# OpenBook_Schematic.net
KiCad netlist of a schematic drawn in EAGLE
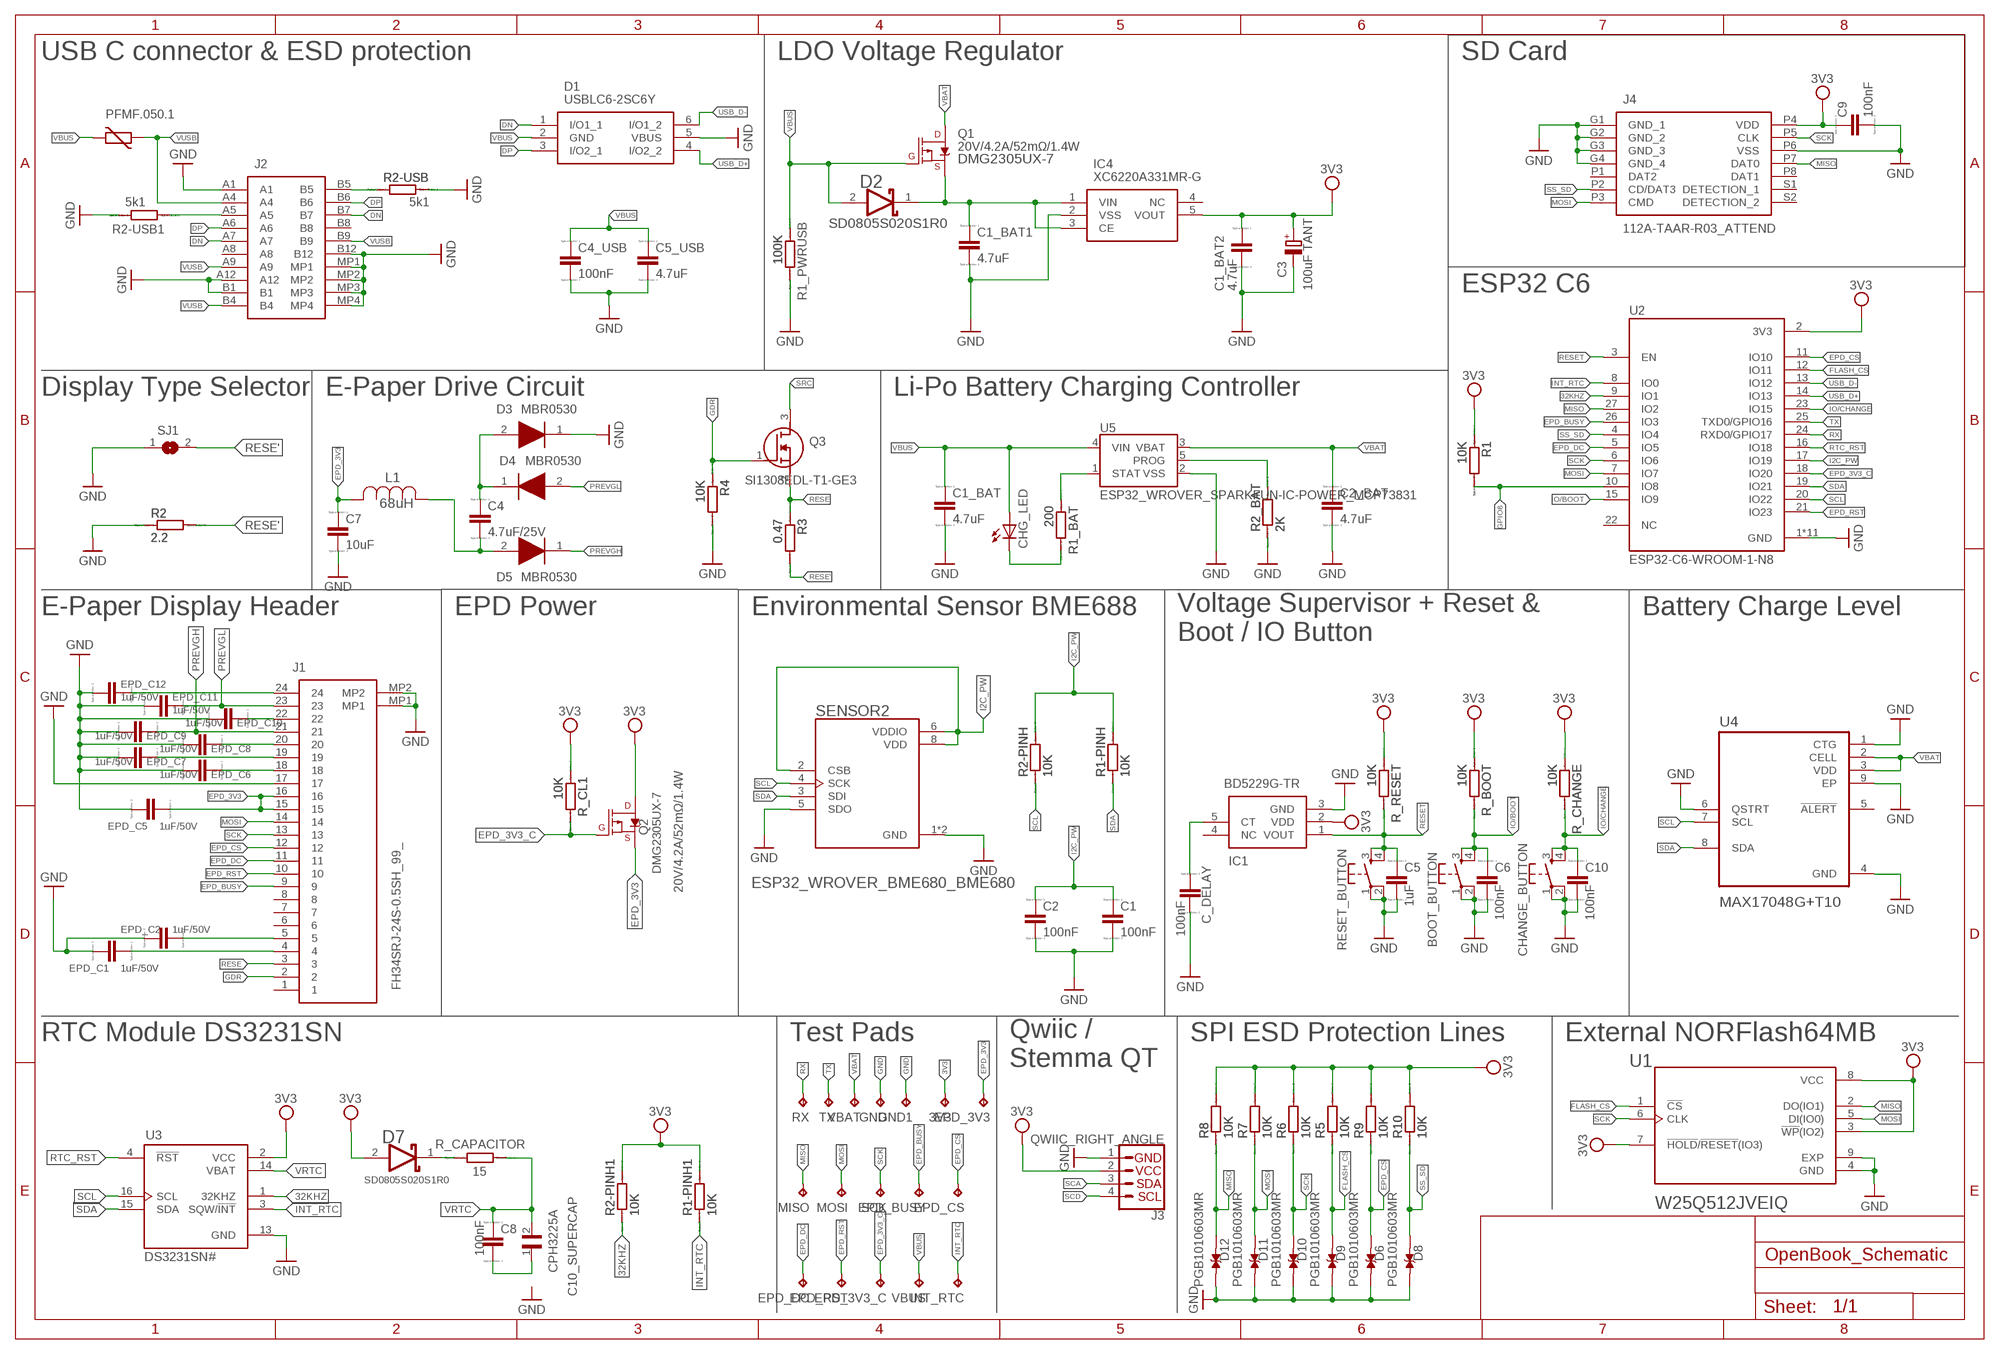
[diagram p0: schematic, sheet 1]

(export (version "E")
  (design (tool "Eeschema 10.0.6"))
  (components
    (comp (ref "3V3")
      (value "TPTP20R")
      (footprint "eagle-import:TP20R")
      (libsource (lib "eagle-import") (part "TPTP20R"))
    )
    (comp (ref "BOOT_BUTTON")
      (value "BUTTON_CUSYOMV1BUTTON")
      (footprint "eagle-import:MYBUTTON")
      (libsource (lib "eagle-import") (part "BUTTON_CUSYOMV1BUTTON"))
    )
    (comp (ref "C1")
      (value "100nF")
      (footprint "eagle-import:ESP32_WROVER_EAGLE-LTSPICE_C0402")
      (libsource (lib "eagle-import") (part "ESP32_WROVER_EAGLE-LTSPICE_CC0402"))
    )
    (comp (ref "C1_BAT")
      (value "4.7uF")
      (footprint "eagle-import:EAGLE-LTSPICE_C0402")
      (libsource (lib "eagle-import") (part "EAGLE-LTSPICE_CC0402"))
    )
    (comp (ref "C1_BAT1")
      (value "4.7uF")
      (footprint "eagle-import:EAGLE-LTSPICE_C0402")
      (libsource (lib "eagle-import") (part "EAGLE-LTSPICE_CC0402"))
    )
    (comp (ref "C1_BAT2")
      (value "4.7uF")
      (footprint "eagle-import:EAGLE-LTSPICE_C0402")
      (libsource (lib "eagle-import") (part "EAGLE-LTSPICE_CC0402"))
    )
    (comp (ref "C2")
      (value "100nF")
      (footprint "eagle-import:ESP32_WROVER_EAGLE-LTSPICE_C0402")
      (libsource (lib "eagle-import") (part "ESP32_WROVER_EAGLE-LTSPICE_CC0402"))
    )
    (comp (ref "C2_BAT")
      (value "4.7uF")
      (footprint "eagle-import:EAGLE-LTSPICE_C0402")
      (libsource (lib "eagle-import") (part "EAGLE-LTSPICE_CC0402"))
    )
    (comp (ref "C3")
      (value "100uF TANT")
      (footprint "eagle-import:RCL_CT3528")
      (libsource (lib "eagle-import") (part "RCL_CPOL-EUCT3528"))
    )
    (comp (ref "C4")
      (value "4.7uF/25V")
      (footprint "eagle-import:EAGLE-LTSPICE_C0402")
      (libsource (lib "eagle-import") (part "EAGLE-LTSPICE_CC0402"))
    )
    (comp (ref "C4_USB")
      (value "100nF")
      (footprint "eagle-import:EAGLE-LTSPICE_C0402")
      (libsource (lib "eagle-import") (part "EAGLE-LTSPICE_CC0402"))
    )
    (comp (ref "C5")
      (value "1uF")
      (footprint "eagle-import:EAGLE-LTSPICE_C0402")
      (libsource (lib "eagle-import") (part "EAGLE-LTSPICE_CC0402"))
    )
    (comp (ref "C5_USB")
      (value "4.7uF")
      (footprint "eagle-import:EAGLE-LTSPICE_C0402")
      (libsource (lib "eagle-import") (part "EAGLE-LTSPICE_CC0402"))
    )
    (comp (ref "C6")
      (value "100nF")
      (footprint "eagle-import:EAGLE-LTSPICE_C0402")
      (libsource (lib "eagle-import") (part "EAGLE-LTSPICE_CC0402"))
    )
    (comp (ref "C7")
      (value "10uF")
      (footprint "eagle-import:EAGLE-LTSPICE_C0402")
      (libsource (lib "eagle-import") (part "EAGLE-LTSPICE_CC0402"))
    )
    (comp (ref "C8")
      (value "100nF")
      (footprint "eagle-import:EAGLE-LTSPICE_C0402")
      (libsource (lib "eagle-import") (part "EAGLE-LTSPICE_CC0402"))
    )
    (comp (ref "C9")
      (value "100nF")
      (footprint "eagle-import:ESP32_WROVER_EAGLE-LTSPICE_C0402")
      (libsource (lib "eagle-import") (part "ESP32_WROVER_EAGLE-LTSPICE_CC0402"))
    )
    (comp (ref "C10")
      (value "100nF")
      (footprint "eagle-import:EAGLE-LTSPICE_C0402")
      (libsource (lib "eagle-import") (part "EAGLE-LTSPICE_CC0402"))
    )
    (comp (ref "C10_SUPERCAP")
      (value "CPH3225A")
      (footprint "eagle-import:CAPCP3225X100N")
      (fields (field (name "MF") "Seiko Instruments"))
      (libsource (lib "eagle-import") (part "CPH3225A"))
    )
    (comp (ref "CHANGE_BUTTON")
      (value "BUTTON_CUSYOMV1BUTTON")
      (footprint "eagle-import:MYBUTTON")
      (libsource (lib "eagle-import") (part "BUTTON_CUSYOMV1BUTTON"))
    )
    (comp (ref "CHG_LED")
      (value "ADAFRUIT_LEDCHIP-LED0603")
      (footprint "eagle-import:ADAFRUIT_CHIP-LED0603")
      (libsource (lib "eagle-import") (part "ADAFRUIT_LEDCHIP-LED0603"))
    )
    (comp (ref "C_DELAY")
      (value "100nF")
      (footprint "eagle-import:ESP32_WROVER_EAGLE-LTSPICE_C0402")
      (libsource (lib "eagle-import") (part "ESP32_WROVER_EAGLE-LTSPICE_CC0402"))
    )
    (comp (ref "D1")
      (value "USBLC6-2SC6Y")
      (footprint "eagle-import:SOT95P280X145-6N")
      (fields (field (name "MF") "STMicroelectronics"))
      (libsource (lib "eagle-import") (part "USBLC6-2SC6Y"))
    )
    (comp (ref "D2")
      (value "ESP32_WROVER_AVX---SD0805S020S1R0_AVX_SD0805S020S1R0_0_0AVX_SD0805S020S1R0_0_0")
      (footprint "eagle-import:ESP32_WROVER_AVX---SD0805S020S1R0_AVX_SD0805S020S1R0_0")
      (fields
        (field (name "DIGIKEY_PART_NUMBER") "478-7800-1-ND")
        (field (name "MF") "AVX")
        (field (name "MOUSER_PART_NUMBER") "581-SD0805S020S1R0")
      )
      (libsource (lib "eagle-import") (part "ESP32_WROVER_AVX---SD0805S020S1R0_AVX_SD0805S020S1R0_0_0AVX_SD0805S020S1R0_0_0"))
    )
    (comp (ref "D3")
      (value "MBR0530")
      (footprint "eagle-import:SOD3716X135N")
      (fields (field (name "MF") "ON Semiconductor"))
      (libsource (lib "eagle-import") (part "MBR0530"))
    )
    (comp (ref "D4")
      (value "MBR0530")
      (footprint "eagle-import:SOD3716X135N")
      (fields (field (name "MF") "ON Semiconductor"))
      (libsource (lib "eagle-import") (part "MBR0530"))
    )
    (comp (ref "D5")
      (value "MBR0530")
      (footprint "eagle-import:SOD3716X135N")
      (fields (field (name "MF") "ON Semiconductor"))
      (libsource (lib "eagle-import") (part "MBR0530"))
    )
    (comp (ref "D6")
      (value "PGB1010603MR")
      (footprint "eagle-import:DIOC1608X36N")
      (fields (field (name "MF") "Littelfuse Inc."))
      (libsource (lib "eagle-import") (part "PGB1010603MR"))
    )
    (comp (ref "D7")
      (value "ESP32_WROVER_AVX---SD0805S020S1R0_AVX_SD0805S020S1R0_0_0AVX_SD0805S020S1R0_0_0")
      (footprint "eagle-import:ESP32_WROVER_AVX---SD0805S020S1R0_AVX_SD0805S020S1R0_0")
      (fields
        (field (name "DIGIKEY_PART_NUMBER") "478-7800-1-ND")
        (field (name "MF") "AVX")
        (field (name "MOUSER_PART_NUMBER") "581-SD0805S020S1R0")
      )
      (libsource (lib "eagle-import") (part "ESP32_WROVER_AVX---SD0805S020S1R0_AVX_SD0805S020S1R0_0_0AVX_SD0805S020S1R0_0_0"))
    )
    (comp (ref "D8")
      (value "PGB1010603MR")
      (footprint "eagle-import:DIOC1608X36N")
      (fields (field (name "MF") "Littelfuse Inc."))
      (libsource (lib "eagle-import") (part "PGB1010603MR"))
    )
    (comp (ref "D9")
      (value "PGB1010603MR")
      (footprint "eagle-import:DIOC1608X36N")
      (fields (field (name "MF") "Littelfuse Inc."))
      (libsource (lib "eagle-import") (part "PGB1010603MR"))
    )
    (comp (ref "D10")
      (value "PGB1010603MR")
      (footprint "eagle-import:DIOC1608X36N")
      (fields (field (name "MF") "Littelfuse Inc."))
      (libsource (lib "eagle-import") (part "PGB1010603MR"))
    )
    (comp (ref "D11")
      (value "PGB1010603MR")
      (footprint "eagle-import:DIOC1608X36N")
      (fields (field (name "MF") "Littelfuse Inc."))
      (libsource (lib "eagle-import") (part "PGB1010603MR"))
    )
    (comp (ref "D12")
      (value "PGB1010603MR")
      (footprint "eagle-import:DIOC1608X36N")
      (fields (field (name "MF") "Littelfuse Inc."))
      (libsource (lib "eagle-import") (part "PGB1010603MR"))
    )
    (comp (ref "EPD_3V3")
      (value "TPTP20R")
      (footprint "eagle-import:TP20R")
      (libsource (lib "eagle-import") (part "TPTP20R"))
    )
    (comp (ref "EPD_3V3_C")
      (value "TPTP20R")
      (footprint "eagle-import:TP20R")
      (libsource (lib "eagle-import") (part "TPTP20R"))
    )
    (comp (ref "EPD_BUSY")
      (value "TPTP20R")
      (footprint "eagle-import:TP20R")
      (libsource (lib "eagle-import") (part "TPTP20R"))
    )
    (comp (ref "EPD_C1")
      (value "1uF/50V")
      (footprint "eagle-import:ESP32_WROVER_EAGLE-LTSPICE_C0402")
      (libsource (lib "eagle-import") (part "ESP32_WROVER_EAGLE-LTSPICE_CC0402"))
    )
    (comp (ref "EPD_C2")
      (value "1uF/50V")
      (footprint "eagle-import:ESP32_WROVER_EAGLE-LTSPICE_C0402")
      (libsource (lib "eagle-import") (part "ESP32_WROVER_EAGLE-LTSPICE_CC0402"))
    )
    (comp (ref "EPD_C5")
      (value "1uF/50V")
      (footprint "eagle-import:ESP32_WROVER_EAGLE-LTSPICE_C0402")
      (libsource (lib "eagle-import") (part "ESP32_WROVER_EAGLE-LTSPICE_CC0402"))
    )
    (comp (ref "EPD_C6")
      (value "1uF/50V")
      (footprint "eagle-import:ESP32_WROVER_EAGLE-LTSPICE_C0402")
      (libsource (lib "eagle-import") (part "ESP32_WROVER_EAGLE-LTSPICE_CC0402"))
    )
    (comp (ref "EPD_C7")
      (value "1uF/50V")
      (footprint "eagle-import:ESP32_WROVER_EAGLE-LTSPICE_C0402")
      (libsource (lib "eagle-import") (part "ESP32_WROVER_EAGLE-LTSPICE_CC0402"))
    )
    (comp (ref "EPD_C8")
      (value "1uF/50V")
      (footprint "eagle-import:ESP32_WROVER_EAGLE-LTSPICE_C0402")
      (libsource (lib "eagle-import") (part "ESP32_WROVER_EAGLE-LTSPICE_CC0402"))
    )
    (comp (ref "EPD_C9")
      (value "1uF/50V")
      (footprint "eagle-import:ESP32_WROVER_EAGLE-LTSPICE_C0402")
      (libsource (lib "eagle-import") (part "ESP32_WROVER_EAGLE-LTSPICE_CC0402"))
    )
    (comp (ref "EPD_C10")
      (value "1uF/50V")
      (footprint "eagle-import:ESP32_WROVER_EAGLE-LTSPICE_C0402")
      (libsource (lib "eagle-import") (part "ESP32_WROVER_EAGLE-LTSPICE_CC0402"))
    )
    (comp (ref "EPD_C11")
      (value "1uF/50V")
      (footprint "eagle-import:ESP32_WROVER_EAGLE-LTSPICE_C0402")
      (libsource (lib "eagle-import") (part "ESP32_WROVER_EAGLE-LTSPICE_CC0402"))
    )
    (comp (ref "EPD_C12")
      (value "1uF/50V")
      (footprint "eagle-import:ESP32_WROVER_EAGLE-LTSPICE_C0402")
      (libsource (lib "eagle-import") (part "ESP32_WROVER_EAGLE-LTSPICE_CC0402"))
    )
    (comp (ref "EPD_CS")
      (value "TPTP20R")
      (footprint "eagle-import:TP20R")
      (libsource (lib "eagle-import") (part "TPTP20R"))
    )
    (comp (ref "EPD_DC")
      (value "TPTP20R")
      (footprint "eagle-import:TP20R")
      (libsource (lib "eagle-import") (part "TPTP20R"))
    )
    (comp (ref "EPD_RST")
      (value "TPTP20R")
      (footprint "eagle-import:TP20R")
      (libsource (lib "eagle-import") (part "TPTP20R"))
    )
    (comp (ref "GND")
      (value "TPTP20R")
      (footprint "eagle-import:TP20R")
      (libsource (lib "eagle-import") (part "TPTP20R"))
    )
    (comp (ref "GND1")
      (value "TPTP20R")
      (footprint "eagle-import:TP20R")
      (libsource (lib "eagle-import") (part "TPTP20R"))
    )
    (comp (ref "IC1")
      (value "BD5229G-TR")
      (footprint "eagle-import:SOT95P280X125-5N")
      (fields (field (name "MOUSER_PART_NUMBER") "755-BD5229G-TR"))
      (libsource (lib "eagle-import") (part "BD5229G-TR"))
    )
    (comp (ref "IC4")
      (value "XC6220A331MR-G")
      (footprint "eagle-import:SOT95P280X120-5N")
      (fields (field (name "MOUSER_PART_NUMBER") "865-XC6220A331MR-G"))
      (libsource (lib "eagle-import") (part "XC6220A331MR-G"))
    )
    (comp (ref "INT_RTC")
      (value "TPTP20R")
      (footprint "eagle-import:TP20R")
      (libsource (lib "eagle-import") (part "TPTP20R"))
    )
    (comp (ref "J1")
      (value "FH34SRJ-24S-0.5SH_99_")
      (footprint "eagle-import:FH34SRJ24S05SH99")
      (fields
        (field (name "MANUFACTURER_PART_NUMBER") "FH34SRJ-24S-0.5SH(99)")
        (field (name "MOUSER_PART_NUMBER") "798-FH34SRJ24S05SH99")
      )
      (libsource (lib "eagle-import") (part "FH34SRJ-24S-0.5SH_99_"))
    )
    (comp (ref "J2")
      (value "SAMACSYS_PARTS_USB4110-GF-A")
      (footprint "eagle-import:SAMACSYS_PARTS_USB4110GFA")
      (fields
        (field (name "MANUFACTURER_PART_NUMBER") "USB4110-GF-A")
        (field (name "MOUSER_PART_NUMBER") "640-USB4110-GF-A")
      )
      (libsource (lib "eagle-import") (part "SAMACSYS_PARTS_USB4110-GF-A"))
    )
    (comp (ref "J3")
      (value "QWIIC_RIGHT_ANGLE")
      (footprint "eagle-import:JST04_1MM_RA")
      (libsource (lib "eagle-import") (part "QWIIC_CONNECTORJS-1MM"))
    )
    (comp (ref "J4")
      (value "112A-TAAR-R03_ATTEND")
      (footprint "eagle-import:112ATAARR03ATTEND")
      (fields (field (name "MANUFACTURER_PART_NUMBER") "112A-TAAR-R03 ATTEND"))
      (libsource (lib "eagle-import") (part "112A-TAAR-R03_ATTEND"))
    )
    (comp (ref "L1")
      (value "68uH")
      (footprint "eagle-import:IND_4828-WE-TPC_WRE")
      (fields
        (field (name "MANUFACTURER_PART_NUMBER") "744043680")
        (field (name "COPYRIGHT") "Copyright (C) 2024 Ultra Librarian. All rights reserved.")
      )
      (libsource (lib "eagle-import") (part "744043680IND_4828-WE-TPC_WRE"))
    )
    (comp (ref "MISO")
      (value "TPTP20R")
      (footprint "eagle-import:TP20R")
      (libsource (lib "eagle-import") (part "TPTP20R"))
    )
    (comp (ref "MOSI")
      (value "TPTP20R")
      (footprint "eagle-import:TP20R")
      (libsource (lib "eagle-import") (part "TPTP20R"))
    )
    (comp (ref "PFMF.050.1")
      (value "ESP32C6_VARISTORCN1812")
      (footprint "eagle-import:ESP32C6_VARISTOR_CT_CN1812")
      (libsource (lib "eagle-import") (part "ESP32C6_VARISTORCN1812"))
    )
    (comp (ref "Q1")
      (value "20V/4.2A/52mΩ/1.4W")
      (footprint "eagle-import:ESP32_WROVER_SPARKFUN-DISCRETESEMI_SOT23-3")
      (libsource (lib "eagle-import") (part "ESP32_WROVER_SPARKFUN-DISCRETESEMI_MOSFET_PCH-DMG2305UX-7"))
    )
    (comp (ref "Q2")
      (value "20V/4.2A/52mΩ/1.4W")
      (footprint "eagle-import:ESP32_WROVER_SPARKFUN-DISCRETESEMI_SOT23-3")
      (libsource (lib "eagle-import") (part "ESP32_WROVER_SPARKFUN-DISCRETESEMI_MOSFET_PCH-DMG2305UX-7"))
    )
    (comp (ref "Q3")
      (value "SI1308EDL-T1-GE3")
      (footprint "eagle-import:SOT65P210X110-3N")
      (fields (field (name "MF") "Vishay Siliconix"))
      (libsource (lib "eagle-import") (part "SI1308EDL-T1-GE3"))
    )
    (comp (ref "R1")
      (value "10K")
      (footprint "eagle-import:ESP32_WROVER_EAGLE-LTSPICE_R0402")
      (libsource (lib "eagle-import") (part "ESP32_WROVER_EAGLE-LTSPICE_RR0402"))
    )
    (comp (ref "R1-PINH")
      (value "10K")
      (footprint "eagle-import:ESP32_WROVER_EAGLE-LTSPICE_R0402")
      (libsource (lib "eagle-import") (part "ESP32_WROVER_EAGLE-LTSPICE_RR0402"))
    )
    (comp (ref "R1-PINH1")
      (value "10K")
      (footprint "eagle-import:ESP32_WROVER_EAGLE-LTSPICE_R0402")
      (libsource (lib "eagle-import") (part "ESP32_WROVER_EAGLE-LTSPICE_RR0402"))
    )
    (comp (ref "R1_BAT")
      (value "200")
      (footprint "eagle-import:ESP32_WROVER_EAGLE-LTSPICE_R0402")
      (libsource (lib "eagle-import") (part "ESP32_WROVER_EAGLE-LTSPICE_RR0402"))
    )
    (comp (ref "R1_PWRUSB")
      (value "100K")
      (footprint "eagle-import:ESP32_WROVER_EAGLE-LTSPICE_R0402")
      (libsource (lib "eagle-import") (part "ESP32_WROVER_EAGLE-LTSPICE_RR0402"))
    )
    (comp (ref "R2")
      (value "2.2")
      (footprint "eagle-import:ESP32_WROVER_EAGLE-LTSPICE_R0402")
      (libsource (lib "eagle-import") (part "ESP32_WROVER_EAGLE-LTSPICE_RR0402"))
    )
    (comp (ref "R2-PINH")
      (value "10K")
      (footprint "eagle-import:ESP32_WROVER_EAGLE-LTSPICE_R0402")
      (libsource (lib "eagle-import") (part "ESP32_WROVER_EAGLE-LTSPICE_RR0402"))
    )
    (comp (ref "R2-PINH1")
      (value "10K")
      (footprint "eagle-import:ESP32_WROVER_EAGLE-LTSPICE_R0402")
      (libsource (lib "eagle-import") (part "ESP32_WROVER_EAGLE-LTSPICE_RR0402"))
    )
    (comp (ref "R2-USB")
      (value "5k1")
      (footprint "eagle-import:ESP32_WROVER_EAGLE-LTSPICE_R0402")
      (libsource (lib "eagle-import") (part "ESP32_WROVER_EAGLE-LTSPICE_RR0402"))
    )
    (comp (ref "R2-USB1")
      (value "5k1")
      (footprint "eagle-import:ESP32_WROVER_EAGLE-LTSPICE_R0402")
      (libsource (lib "eagle-import") (part "ESP32_WROVER_EAGLE-LTSPICE_RR0402"))
    )
    (comp (ref "R2_BAT")
      (value "2K")
      (footprint "eagle-import:ESP32_WROVER_EAGLE-LTSPICE_R0402")
      (libsource (lib "eagle-import") (part "ESP32_WROVER_EAGLE-LTSPICE_RR0402"))
    )
    (comp (ref "R3")
      (value "0.47")
      (footprint "eagle-import:ESP32_WROVER_EAGLE-LTSPICE_R0402")
      (libsource (lib "eagle-import") (part "ESP32_WROVER_EAGLE-LTSPICE_RR0402"))
    )
    (comp (ref "R4")
      (value "10K")
      (footprint "eagle-import:ESP32_WROVER_EAGLE-LTSPICE_R0402")
      (libsource (lib "eagle-import") (part "ESP32_WROVER_EAGLE-LTSPICE_RR0402"))
    )
    (comp (ref "R5")
      (value "10K")
      (footprint "eagle-import:ESP32_WROVER_EAGLE-LTSPICE_R0402")
      (libsource (lib "eagle-import") (part "ESP32_WROVER_EAGLE-LTSPICE_RR0402"))
    )
    (comp (ref "R6")
      (value "10K")
      (footprint "eagle-import:ESP32_WROVER_EAGLE-LTSPICE_R0402")
      (libsource (lib "eagle-import") (part "ESP32_WROVER_EAGLE-LTSPICE_RR0402"))
    )
    (comp (ref "R7")
      (value "10K")
      (footprint "eagle-import:ESP32_WROVER_EAGLE-LTSPICE_R0402")
      (libsource (lib "eagle-import") (part "ESP32_WROVER_EAGLE-LTSPICE_RR0402"))
    )
    (comp (ref "R8")
      (value "10K")
      (footprint "eagle-import:ESP32_WROVER_EAGLE-LTSPICE_R0402")
      (libsource (lib "eagle-import") (part "ESP32_WROVER_EAGLE-LTSPICE_RR0402"))
    )
    (comp (ref "R9")
      (value "10K")
      (footprint "eagle-import:ESP32_WROVER_EAGLE-LTSPICE_R0402")
      (libsource (lib "eagle-import") (part "ESP32_WROVER_EAGLE-LTSPICE_RR0402"))
    )
    (comp (ref "R10")
      (value "10K")
      (footprint "eagle-import:ESP32_WROVER_EAGLE-LTSPICE_R0402")
      (libsource (lib "eagle-import") (part "ESP32_WROVER_EAGLE-LTSPICE_RR0402"))
    )
    (comp (ref "RESET_BUTTON")
      (value "BUTTON_CUSYOMV1BUTTON")
      (footprint "eagle-import:MYBUTTON")
      (libsource (lib "eagle-import") (part "BUTTON_CUSYOMV1BUTTON"))
    )
    (comp (ref "RX")
      (value "TPTP20R")
      (footprint "eagle-import:TP20R")
      (libsource (lib "eagle-import") (part "TPTP20R"))
    )
    (comp (ref "R_BOOT")
      (value "10K")
      (footprint "eagle-import:ESP32_WROVER_EAGLE-LTSPICE_R0402")
      (libsource (lib "eagle-import") (part "ESP32_WROVER_EAGLE-LTSPICE_RR0402"))
    )
    (comp (ref "R_CAPACITOR")
      (value "15")
      (footprint "eagle-import:ESP32_WROVER_EAGLE-LTSPICE_R0402")
      (libsource (lib "eagle-import") (part "ESP32_WROVER_EAGLE-LTSPICE_RR0402"))
    )
    (comp (ref "R_CHANGE")
      (value "10K")
      (footprint "eagle-import:ESP32_WROVER_EAGLE-LTSPICE_R0402")
      (libsource (lib "eagle-import") (part "ESP32_WROVER_EAGLE-LTSPICE_RR0402"))
    )
    (comp (ref "R_CL1")
      (value "10K")
      (footprint "eagle-import:ESP32_WROVER_EAGLE-LTSPICE_R0402")
      (libsource (lib "eagle-import") (part "ESP32_WROVER_EAGLE-LTSPICE_RR0402"))
    )
    (comp (ref "R_RESET")
      (value "10K")
      (footprint "eagle-import:ESP32_WROVER_EAGLE-LTSPICE_R0402")
      (libsource (lib "eagle-import") (part "ESP32_WROVER_EAGLE-LTSPICE_RR0402"))
    )
    (comp (ref "SCK")
      (value "TPTP20R")
      (footprint "eagle-import:TP20R")
      (libsource (lib "eagle-import") (part "TPTP20R"))
    )
    (comp (ref "SENSOR2")
      (value "ESP32_WROVER_BME680_BME680")
      (footprint "eagle-import:ESP32_WROVER_BME680_PSON80P300X300X100-8N")
      (fields (field (name "MF") "Bosch Sensortec") (field (name "MP") "BME680"))
      (libsource (lib "eagle-import") (part "ESP32_WROVER_BME680_BME680"))
    )
    (comp (ref "SJ1") (value "SJ") (footprint "eagle-import:SJ") (libsource (lib "eagle-import") (part "SJ")))
    (comp (ref "TX")
      (value "TPTP20R")
      (footprint "eagle-import:TP20R")
      (libsource (lib "eagle-import") (part "TPTP20R"))
    )
    (comp (ref "U1")
      (value "W25Q512JVEIQ")
      (footprint "eagle-import:SON127P600X800X80-9N")
      (fields (field (name "MF") "Winbond Electronics"))
      (libsource (lib "eagle-import") (part "W25Q512JVEIQ"))
    )
    (comp (ref "U2")
      (value "ESP32-C6-WROOM-1-N8")
      (footprint "eagle-import:XCVR_ESP32-C6-WROOM-1-N8")
      (fields (field (name "MF") "Espressif Systems"))
      (libsource (lib "eagle-import") (part "ESP32-C6-WROOM-1-N8"))
    )
    (comp (ref "U3")
      (value "DS3231SN#")
      (footprint "eagle-import:SOIC127P1032X265-16N")
      (fields (field (name "MF") "Analog Devices"))
      (libsource (lib "eagle-import") (part "DS3231SN#"))
    )
    (comp (ref "U4")
      (value "MAX17048G+T10")
      (footprint "eagle-import:SON50P200X200X80-9N")
      (fields (field (name "MF") "Analog Devices"))
      (libsource (lib "eagle-import") (part "MAX17048G+T10"))
    )
    (comp (ref "U5")
      (value "ESP32_WROVER_SPARKFUN-IC-POWER_MCP73831")
      (footprint "eagle-import:ESP32_WROVER_SPARKFUN-IC-POWER_SOT23-5")
      (libsource (lib "eagle-import") (part "ESP32_WROVER_SPARKFUN-IC-POWER_MCP73831"))
    )
    (comp (ref "VBAT")
      (value "TPTP20R")
      (footprint "eagle-import:TP20R")
      (libsource (lib "eagle-import") (part "TPTP20R"))
    )
    (comp (ref "VBUS")
      (value "TPTP20R")
      (footprint "eagle-import:TP20R")
      (libsource (lib "eagle-import") (part "TPTP20R"))
    )
  )
  (nets
    (net (code "1") (name "3V3") (class "Default")
      (node (ref "3V3") (pin "TP") (pinfunction "TP_TP") (pintype "input"))
      (node (ref "C1_BAT2") (pin "1") (pinfunction "1_1") (pintype "passive"))
      (node (ref "C3") (pin "+") (pinfunction "+_+") (pintype "passive"))
      (node (ref "C9") (pin "1") (pinfunction "1_1") (pintype "passive"))
      (node (ref "D7") (pin "2") (pinfunction "ANODE_2") (pintype "bidirectional"))
      (node (ref "IC1") (pin "2") (pinfunction "VDD_2") (pintype "bidirectional"))
      (node (ref "IC4") (pin "5") (pinfunction "VOUT_5") (pintype "bidirectional"))
      (node (ref "J3") (pin "2") (pinfunction "2_2") (pintype "power_in"))
      (node (ref "J4") (pin "P4") (pinfunction "VDD_P4") (pintype "bidirectional"))
      (node (ref "Q2") (pin "3") (pinfunction "D_3") (pintype "bidirectional"))
      (node (ref "R1") (pin "1") (pinfunction "1_1") (pintype "passive"))
      (node (ref "R1-PINH1") (pin "2") (pinfunction "2_2") (pintype "passive"))
      (node (ref "R10") (pin "2") (pinfunction "2_2") (pintype "passive"))
      (node (ref "R2-PINH1") (pin "2") (pinfunction "2_2") (pintype "passive"))
      (node (ref "R5") (pin "2") (pinfunction "2_2") (pintype "passive"))
      (node (ref "R6") (pin "2") (pinfunction "2_2") (pintype "passive"))
      (node (ref "R7") (pin "2") (pinfunction "2_2") (pintype "passive"))
      (node (ref "R8") (pin "2") (pinfunction "2_2") (pintype "passive"))
      (node (ref "R9") (pin "2") (pinfunction "2_2") (pintype "passive"))
      (node (ref "R_BOOT") (pin "1") (pinfunction "1_1") (pintype "passive"))
      (node (ref "R_CHANGE") (pin "1") (pinfunction "1_1") (pintype "passive"))
      (node (ref "R_CL1") (pin "1") (pinfunction "1_1") (pintype "passive"))
      (node (ref "R_RESET") (pin "1") (pinfunction "1_1") (pintype "passive"))
      (node (ref "U1") (pin "3") (pinfunction "~{WP}(IO2)_3") (pintype "bidirectional"))
      (node (ref "U1") (pin "7") (pinfunction "~{HOLD}/~{RESET}(IO3)_7") (pintype "bidirectional"))
      (node (ref "U1") (pin "8") (pinfunction "VCC_8") (pintype "power_in"))
      (node (ref "U2") (pin "2") (pinfunction "3V3_2") (pintype "power_in"))
      (node (ref "U3") (pin "2") (pinfunction "VCC_2") (pintype "power_in"))
    )
    (net (code "2") (name "32KHZ") (class "Default")
      (node (ref "R2-PINH1") (pin "1") (pinfunction "1_1") (pintype "passive"))
      (node (ref "U2") (pin "9") (pinfunction "IO1_9") (pintype "bidirectional"))
      (node (ref "U3") (pin "1") (pinfunction "32KHZ_1") (pintype "output"))
    )
    (net (code "3") (name "DN") (class "Default")
      (node (ref "D1") (pin "1") (pinfunction "I/O1_1_1") (pintype "bidirectional"))
      (node (ref "J2") (pin "A7") (pinfunction "A7_A7") (pintype "bidirectional"))
      (node (ref "J2") (pin "B7") (pinfunction "B7_B7") (pintype "bidirectional"))
    )
    (net (code "4") (name "DP") (class "Default")
      (node (ref "D1") (pin "3") (pinfunction "I/O2_1_3") (pintype "bidirectional"))
      (node (ref "J2") (pin "A6") (pinfunction "A6_A6") (pintype "bidirectional"))
      (node (ref "J2") (pin "B6") (pinfunction "B6_B6") (pintype "bidirectional"))
    )
    (net (code "5") (name "EPD_3V3") (class "Default")
      (node (ref "C7") (pin "1") (pinfunction "1_1") (pintype "passive"))
      (node (ref "EPD_3V3") (pin "TP") (pinfunction "TP_TP") (pintype "input"))
      (node (ref "EPD_C5") (pin "1") (pinfunction "1_1") (pintype "passive"))
      (node (ref "J1") (pin "15") (pinfunction "15_15") (pintype "bidirectional"))
      (node (ref "J1") (pin "16") (pinfunction "16_16") (pintype "bidirectional"))
      (node (ref "L1") (pin "2") (pinfunction "2_2") (pintype "passive"))
      (node (ref "Q2") (pin "2") (pinfunction "S_2") (pintype "bidirectional"))
    )
    (net (code "6") (name "EPD_3V3_C") (class "Default")
      (node (ref "EPD_3V3_C") (pin "TP") (pinfunction "TP_TP") (pintype "input"))
      (node (ref "Q2") (pin "1") (pinfunction "G_1") (pintype "bidirectional"))
      (node (ref "R_CL1") (pin "2") (pinfunction "2_2") (pintype "passive"))
      (node (ref "U2") (pin "18") (pinfunction "IO20_18") (pintype "bidirectional"))
    )
    (net (code "7") (name "EPD_BUSY") (class "Default")
      (node (ref "EPD_BUSY") (pin "TP") (pinfunction "TP_TP") (pintype "input"))
      (node (ref "J1") (pin "9") (pinfunction "9_9") (pintype "bidirectional"))
      (node (ref "U2") (pin "26") (pinfunction "IO3_26") (pintype "bidirectional"))
    )
    (net (code "8") (name "EPD_CS") (class "Default")
      (node (ref "D6") (pin "2") (pinfunction "2_2") (pintype "passive"))
      (node (ref "EPD_CS") (pin "TP") (pinfunction "TP_TP") (pintype "input"))
      (node (ref "J1") (pin "12") (pinfunction "12_12") (pintype "bidirectional"))
      (node (ref "R9") (pin "1") (pinfunction "1_1") (pintype "passive"))
      (node (ref "U2") (pin "11") (pinfunction "IO10_11") (pintype "bidirectional"))
    )
    (net (code "9") (name "EPD_DC") (class "Default")
      (node (ref "EPD_DC") (pin "TP") (pinfunction "TP_TP") (pintype "input"))
      (node (ref "J1") (pin "11") (pinfunction "11_11") (pintype "bidirectional"))
      (node (ref "U2") (pin "5") (pinfunction "IO5_5") (pintype "bidirectional"))
    )
    (net (code "10") (name "EPD_RST") (class "Default")
      (node (ref "EPD_RST") (pin "TP") (pinfunction "TP_TP") (pintype "input"))
      (node (ref "J1") (pin "10") (pinfunction "10_10") (pintype "bidirectional"))
      (node (ref "U2") (pin "21") (pinfunction "IO23_21") (pintype "bidirectional"))
    )
    (net (code "11") (name "FLASH_CS") (class "Default")
      (node (ref "D9") (pin "2") (pinfunction "2_2") (pintype "passive"))
      (node (ref "R5") (pin "1") (pinfunction "1_1") (pintype "passive"))
      (node (ref "U1") (pin "1") (pinfunction "~{CS}_1") (pintype "input"))
      (node (ref "U2") (pin "12") (pinfunction "IO11_12") (pintype "bidirectional"))
    )
    (net (code "12") (name "GDR") (class "Default")
      (node (ref "J1") (pin "2") (pinfunction "2_2") (pintype "bidirectional"))
      (node (ref "Q3") (pin "1") (pinfunction "G_1") (pintype "bidirectional"))
      (node (ref "R4") (pin "1") (pinfunction "1_1") (pintype "passive"))
    )
    (net (code "13") (name "GND") (class "Default")
      (node (ref "BOOT_BUTTON") (pin "1") (pinfunction "1_1") (pintype "passive"))
      (node (ref "BOOT_BUTTON") (pin "2") (pinfunction "2_2") (pintype "passive"))
      (node (ref "C1") (pin "2") (pinfunction "2_2") (pintype "passive"))
      (node (ref "C10") (pin "2") (pinfunction "2_2") (pintype "passive"))
      (node (ref "C1_BAT") (pin "2") (pinfunction "2_2") (pintype "passive"))
      (node (ref "C1_BAT1") (pin "2") (pinfunction "2_2") (pintype "passive"))
      (node (ref "C1_BAT2") (pin "2") (pinfunction "2_2") (pintype "passive"))
      (node (ref "C2") (pin "2") (pinfunction "2_2") (pintype "passive"))
      (node (ref "C2_BAT") (pin "2") (pinfunction "2_2") (pintype "passive"))
      (node (ref "C3") (pin "-") (pinfunction "-_-") (pintype "passive"))
      (node (ref "C4_USB") (pin "2") (pinfunction "2_2") (pintype "passive"))
      (node (ref "C5") (pin "2") (pinfunction "2_2") (pintype "passive"))
      (node (ref "C5_USB") (pin "2") (pinfunction "2_2") (pintype "passive"))
      (node (ref "C6") (pin "2") (pinfunction "2_2") (pintype "passive"))
      (node (ref "C7") (pin "2") (pinfunction "2_2") (pintype "passive"))
      (node (ref "C9") (pin "2") (pinfunction "2_2") (pintype "passive"))
      (node (ref "CHANGE_BUTTON") (pin "1") (pinfunction "1_1") (pintype "passive"))
      (node (ref "CHANGE_BUTTON") (pin "2") (pinfunction "2_2") (pintype "passive"))
      (node (ref "C_DELAY") (pin "2") (pinfunction "2_2") (pintype "passive"))
      (node (ref "D1") (pin "5") (pinfunction "VBUS_5") (pintype "bidirectional"))
      (node (ref "D10") (pin "1") (pinfunction "1_1") (pintype "passive"))
      (node (ref "D11") (pin "1") (pinfunction "1_1") (pintype "passive"))
      (node (ref "D12") (pin "1") (pinfunction "1_1") (pintype "passive"))
      (node (ref "D3") (pin "1") (pinfunction "K_1") (pintype "bidirectional"))
      (node (ref "D6") (pin "1") (pinfunction "1_1") (pintype "passive"))
      (node (ref "D8") (pin "1") (pinfunction "1_1") (pintype "passive"))
      (node (ref "D9") (pin "1") (pinfunction "1_1") (pintype "passive"))
      (node (ref "EPD_C1") (pin "2") (pinfunction "2_2") (pintype "passive"))
      (node (ref "EPD_C10") (pin "2") (pinfunction "2_2") (pintype "passive"))
      (node (ref "EPD_C11") (pin "2") (pinfunction "2_2") (pintype "passive"))
      (node (ref "EPD_C12") (pin "2") (pinfunction "2_2") (pintype "passive"))
      (node (ref "EPD_C2") (pin "2") (pinfunction "2_2") (pintype "passive"))
      (node (ref "EPD_C5") (pin "2") (pinfunction "2_2") (pintype "passive"))
      (node (ref "EPD_C6") (pin "2") (pinfunction "2_2") (pintype "passive"))
      (node (ref "EPD_C7") (pin "2") (pinfunction "2_2") (pintype "passive"))
      (node (ref "EPD_C8") (pin "2") (pinfunction "2_2") (pintype "passive"))
      (node (ref "EPD_C9") (pin "2") (pinfunction "2_2") (pintype "passive"))
      (node (ref "GND") (pin "TP") (pinfunction "TP_TP") (pintype "input"))
      (node (ref "GND1") (pin "TP") (pinfunction "TP_TP") (pintype "input"))
      (node (ref "IC1") (pin "3") (pinfunction "GND_3") (pintype "bidirectional"))
      (node (ref "IC4") (pin "2") (pinfunction "VSS_2") (pintype "bidirectional"))
      (node (ref "J1") (pin "17") (pinfunction "17_17") (pintype "bidirectional"))
      (node (ref "J1") (pin "MP1") (pinfunction "MP1_MP1") (pintype "bidirectional"))
      (node (ref "J1") (pin "MP2") (pinfunction "MP2_MP2") (pintype "bidirectional"))
      (node (ref "J2") (pin "A1") (pinfunction "A1_A1") (pintype "bidirectional"))
      (node (ref "J2") (pin "A12") (pinfunction "A12_A12") (pintype "bidirectional"))
      (node (ref "J2") (pin "B1") (pinfunction "B1_B1") (pintype "bidirectional"))
      (node (ref "J2") (pin "B12") (pinfunction "B12_B12") (pintype "bidirectional"))
      (node (ref "J2") (pin "MP1") (pinfunction "MP1_MP1") (pintype "bidirectional"))
      (node (ref "J2") (pin "MP2") (pinfunction "MP2_MP2") (pintype "bidirectional"))
      (node (ref "J2") (pin "MP3") (pinfunction "MP3_MP3") (pintype "bidirectional"))
      (node (ref "J2") (pin "MP4") (pinfunction "MP4_MP4") (pintype "bidirectional"))
      (node (ref "J3") (pin "1") (pinfunction "1_1") (pintype "power_in"))
      (node (ref "J4") (pin "G1") (pinfunction "GND_1_G1") (pintype "bidirectional"))
      (node (ref "J4") (pin "G2") (pinfunction "GND_2_G2") (pintype "bidirectional"))
      (node (ref "J4") (pin "G3") (pinfunction "GND_3_G3") (pintype "bidirectional"))
      (node (ref "J4") (pin "G4") (pinfunction "GND_4_G4") (pintype "bidirectional"))
      (node (ref "J4") (pin "P6") (pinfunction "VSS_P6") (pintype "bidirectional"))
      (node (ref "R1_PWRUSB") (pin "2") (pinfunction "2_2") (pintype "passive"))
      (node (ref "R2") (pin "1") (pinfunction "1_1") (pintype "passive"))
      (node (ref "R2-USB") (pin "2") (pinfunction "2_2") (pintype "passive"))
      (node (ref "R2-USB1") (pin "1") (pinfunction "1_1") (pintype "passive"))
      (node (ref "R2_BAT") (pin "1") (pinfunction "1_1") (pintype "passive"))
      (node (ref "R4") (pin "2") (pinfunction "2_2") (pintype "passive"))
      (node (ref "RESET_BUTTON") (pin "1") (pinfunction "1_1") (pintype "passive"))
      (node (ref "RESET_BUTTON") (pin "2") (pinfunction "2_2") (pintype "passive"))
      (node (ref "SENSOR2") (pin "1") (pinfunction "GND_1") (pintype "power_in"))
      (node (ref "SENSOR2") (pin "5") (pinfunction "SDO_5") (pintype "bidirectional"))
      (node (ref "SENSOR2") (pin "7") (pinfunction "GND_7") (pintype "power_in"))
      (node (ref "SJ1") (pin "1") (pinfunction "1_1") (pintype "passive"))
      (node (ref "U1") (pin "4") (pinfunction "GND_4") (pintype "power_in"))
      (node (ref "U1") (pin "9") (pinfunction "EXP_9") (pintype "passive"))
      (node (ref "U2") (pin "1") (pinfunction "GND_1") (pintype "power_in"))
      (node (ref "U2") (pin "28") (pinfunction "GND_28") (pintype "power_in"))
      (node (ref "U2") (pin "29_1") (pinfunction "GND_29_1") (pintype "power_in"))
      (node (ref "U2") (pin "29_2") (pinfunction "GND_29_2") (pintype "power_in"))
      (node (ref "U2") (pin "29_3") (pinfunction "GND_29_3") (pintype "power_in"))
      (node (ref "U2") (pin "29_4") (pinfunction "GND_29_4") (pintype "power_in"))
      (node (ref "U2") (pin "29_5") (pinfunction "GND_29_5") (pintype "power_in"))
      (node (ref "U2") (pin "29_6") (pinfunction "GND_29_6") (pintype "power_in"))
      (node (ref "U2") (pin "29_7") (pinfunction "GND_29_7") (pintype "power_in"))
      (node (ref "U2") (pin "29_8") (pinfunction "GND_29_8") (pintype "power_in"))
      (node (ref "U2") (pin "29_9") (pinfunction "GND_29_9") (pintype "power_in"))
      (node (ref "U3") (pin "13") (pinfunction "GND_13") (pintype "power_in"))
      (node (ref "U4") (pin "1") (pinfunction "CTG_1") (pintype "power_in"))
      (node (ref "U4") (pin "4") (pinfunction "GND_4") (pintype "power_in"))
      (node (ref "U4") (pin "6") (pinfunction "QSTRT_6") (pintype "input"))
      (node (ref "U4") (pin "9") (pinfunction "EP_9") (pintype "power_in"))
      (node (ref "U5") (pin "2") (pinfunction "VSS_2") (pintype "power_in"))
    )
    (net (code "14") (name "GPIO8") (class "Default")
      (node (ref "R1") (pin "2") (pinfunction "2_2") (pintype "passive"))
      (node (ref "U2") (pin "10") (pinfunction "IO8_10") (pintype "bidirectional"))
    )
    (net (code "15") (name "I2C_PW") (class "Default")
      (node (ref "C1") (pin "1") (pinfunction "1_1") (pintype "passive"))
      (node (ref "C2") (pin "1") (pinfunction "1_1") (pintype "passive"))
      (node (ref "R1-PINH") (pin "2") (pinfunction "2_2") (pintype "passive"))
      (node (ref "R2-PINH") (pin "2") (pinfunction "2_2") (pintype "passive"))
      (node (ref "SENSOR2") (pin "2") (pinfunction "CSB_2") (pintype "input"))
      (node (ref "SENSOR2") (pin "6") (pinfunction "VDDIO_6") (pintype "power_in"))
      (node (ref "SENSOR2") (pin "8") (pinfunction "VDD_8") (pintype "power_in"))
      (node (ref "U2") (pin "17") (pinfunction "IO19_17") (pintype "bidirectional"))
    )
    (net (code "16") (name "INT_RTC") (class "Default")
      (node (ref "INT_RTC") (pin "TP") (pinfunction "TP_TP") (pintype "input"))
      (node (ref "R1-PINH1") (pin "1") (pinfunction "1_1") (pintype "passive"))
      (node (ref "U2") (pin "8") (pinfunction "IO0_8") (pintype "bidirectional"))
      (node (ref "U3") (pin "3") (pinfunction "SQW/~{INT}_3") (pintype "output"))
    )
    (net (code "17") (name "IO{slash}BOOT") (class "Default")
      (node (ref "BOOT_BUTTON") (pin "3") (pinfunction "3_3") (pintype "passive"))
      (node (ref "BOOT_BUTTON") (pin "4") (pinfunction "4_4") (pintype "passive"))
      (node (ref "C6") (pin "1") (pinfunction "1_1") (pintype "passive"))
      (node (ref "R_BOOT") (pin "2") (pinfunction "2_2") (pintype "passive"))
      (node (ref "U2") (pin "15") (pinfunction "IO9_15") (pintype "bidirectional"))
    )
    (net (code "18") (name "IO{slash}CHANGE") (class "Default")
      (node (ref "C10") (pin "1") (pinfunction "1_1") (pintype "passive"))
      (node (ref "CHANGE_BUTTON") (pin "3") (pinfunction "3_3") (pintype "passive"))
      (node (ref "CHANGE_BUTTON") (pin "4") (pinfunction "4_4") (pintype "passive"))
      (node (ref "R_CHANGE") (pin "2") (pinfunction "2_2") (pintype "passive"))
      (node (ref "U2") (pin "23") (pinfunction "IO15_23") (pintype "bidirectional"))
    )
    (net (code "19") (name "MISO") (class "Default")
      (node (ref "D12") (pin "2") (pinfunction "2_2") (pintype "passive"))
      (node (ref "J4") (pin "P7") (pinfunction "DAT0_P7") (pintype "bidirectional"))
      (node (ref "MISO") (pin "TP") (pinfunction "TP_TP") (pintype "input"))
      (node (ref "R8") (pin "1") (pinfunction "1_1") (pintype "passive"))
      (node (ref "U1") (pin "2") (pinfunction "DO(IO1)_2") (pintype "bidirectional"))
      (node (ref "U2") (pin "27") (pinfunction "IO2_27") (pintype "bidirectional"))
    )
    (net (code "20") (name "MOSI") (class "Default")
      (node (ref "D11") (pin "2") (pinfunction "2_2") (pintype "passive"))
      (node (ref "J1") (pin "14") (pinfunction "14_14") (pintype "bidirectional"))
      (node (ref "J4") (pin "P3") (pinfunction "CMD_P3") (pintype "bidirectional"))
      (node (ref "MOSI") (pin "TP") (pinfunction "TP_TP") (pintype "input"))
      (node (ref "R7") (pin "1") (pinfunction "1_1") (pintype "passive"))
      (node (ref "U1") (pin "5") (pinfunction "DI(IO0)_5") (pintype "bidirectional"))
      (node (ref "U2") (pin "7") (pinfunction "IO7_7") (pintype "bidirectional"))
    )
    (net (code "21") (name "Net-(C10_SUPERCAP-Pad1)") (class "Default")
      (node (ref "C10_SUPERCAP") (pin "1") (pinfunction "1_1") (pintype "passive"))
      (node (ref "C8") (pin "2") (pinfunction "2_2") (pintype "passive"))
    )
    (net (code "22") (name "Net-(CHG_LED-PadC)") (class "Default")
      (node (ref "CHG_LED") (pin "C") (pinfunction "C_C") (pintype "passive"))
      (node (ref "R1_BAT") (pin "2") (pinfunction "2_2") (pintype "passive"))
    )
    (net (code "23") (name "Net-(D2-CATHODE)") (class "Default")
      (node (ref "C1_BAT1") (pin "1") (pinfunction "1_1") (pintype "passive"))
      (node (ref "D2") (pin "1") (pinfunction "CATHODE_1") (pintype "bidirectional"))
      (node (ref "IC4") (pin "1") (pinfunction "VIN_1") (pintype "bidirectional"))
      (node (ref "IC4") (pin "3") (pinfunction "CE_3") (pintype "bidirectional"))
      (node (ref "Q1") (pin "2") (pinfunction "S_2") (pintype "bidirectional"))
    )
    (net (code "24") (name "Net-(D3-A)") (class "Default")
      (node (ref "C4") (pin "1") (pinfunction "1_1") (pintype "passive"))
      (node (ref "D3") (pin "2") (pinfunction "A_2") (pintype "bidirectional"))
      (node (ref "D4") (pin "1") (pinfunction "K_1") (pintype "bidirectional"))
    )
    (net (code "25") (name "Net-(D5-A)") (class "Default")
      (node (ref "C4") (pin "2") (pinfunction "2_2") (pintype "passive"))
      (node (ref "D5") (pin "2") (pinfunction "A_2") (pintype "bidirectional"))
      (node (ref "L1") (pin "1") (pinfunction "1_1") (pintype "passive"))
    )
    (net (code "26") (name "Net-(D7-CATHODE)") (class "Default")
      (node (ref "D7") (pin "1") (pinfunction "CATHODE_1") (pintype "bidirectional"))
      (node (ref "R_CAPACITOR") (pin "2") (pinfunction "2_2") (pintype "passive"))
    )
    (net (code "27") (name "Net-(EPD_C1-Pad1)") (class "Default")
      (node (ref "EPD_C1") (pin "1") (pinfunction "1_1") (pintype "passive"))
      (node (ref "J1") (pin "4") (pinfunction "4_4") (pintype "bidirectional"))
    )
    (net (code "28") (name "Net-(EPD_C2-Pad1)") (class "Default")
      (node (ref "EPD_C2") (pin "1") (pinfunction "1_1") (pintype "passive"))
      (node (ref "J1") (pin "5") (pinfunction "5_5") (pintype "bidirectional"))
    )
    (net (code "29") (name "Net-(EPD_C6-Pad1)") (class "Default")
      (node (ref "EPD_C6") (pin "1") (pinfunction "1_1") (pintype "passive"))
      (node (ref "J1") (pin "18") (pinfunction "18_18") (pintype "bidirectional"))
    )
    (net (code "30") (name "Net-(EPD_C7-Pad1)") (class "Default")
      (node (ref "EPD_C7") (pin "1") (pinfunction "1_1") (pintype "passive"))
      (node (ref "J1") (pin "19") (pinfunction "19_19") (pintype "bidirectional"))
    )
    (net (code "31") (name "Net-(EPD_C8-Pad1)") (class "Default")
      (node (ref "EPD_C8") (pin "1") (pinfunction "1_1") (pintype "passive"))
      (node (ref "J1") (pin "20") (pinfunction "20_20") (pintype "bidirectional"))
    )
    (net (code "32") (name "Net-(EPD_C10-Pad1)") (class "Default")
      (node (ref "EPD_C10") (pin "1") (pinfunction "1_1") (pintype "passive"))
      (node (ref "J1") (pin "22") (pinfunction "22_22") (pintype "bidirectional"))
    )
    (net (code "33") (name "Net-(EPD_C12-Pad1)") (class "Default")
      (node (ref "EPD_C12") (pin "1") (pinfunction "1_1") (pintype "passive"))
      (node (ref "J1") (pin "24") (pinfunction "24_24") (pintype "bidirectional"))
    )
    (net (code "34") (name "Net-(IC1-CT)") (class "Default")
      (node (ref "C_DELAY") (pin "1") (pinfunction "1_1") (pintype "passive"))
      (node (ref "IC1") (pin "5") (pinfunction "CT_5") (pintype "bidirectional"))
    )
    (net (code "35") (name "Net-(J2-PadA5)") (class "Default")
      (node (ref "J2") (pin "A5") (pinfunction "A5_A5") (pintype "bidirectional"))
      (node (ref "R2-USB1") (pin "2") (pinfunction "2_2") (pintype "passive"))
    )
    (net (code "36") (name "Net-(J2-PadB5)") (class "Default")
      (node (ref "J2") (pin "B5") (pinfunction "B5_B5") (pintype "bidirectional"))
      (node (ref "R2-USB") (pin "1") (pinfunction "1_1") (pintype "passive"))
    )
    (net (code "37") (name "Net-(U5-PROG)") (class "Default")
      (node (ref "R2_BAT") (pin "2") (pinfunction "2_2") (pintype "passive"))
      (node (ref "U5") (pin "5") (pinfunction "PROG_5") (pintype "input"))
    )
    (net (code "38") (name "Net-(U5-STAT)") (class "Default")
      (node (ref "R1_BAT") (pin "1") (pinfunction "1_1") (pintype "passive"))
      (node (ref "U5") (pin "1") (pinfunction "STAT_1") (pintype "output"))
    )
    (net (code "39") (name "PREVGH") (class "Default")
      (node (ref "D5") (pin "1") (pinfunction "K_1") (pintype "bidirectional"))
      (node (ref "EPD_C9") (pin "1") (pinfunction "1_1") (pintype "passive"))
      (node (ref "J1") (pin "21") (pinfunction "21_21") (pintype "bidirectional"))
    )
    (net (code "40") (name "PREVGL") (class "Default")
      (node (ref "D4") (pin "2") (pinfunction "A_2") (pintype "bidirectional"))
      (node (ref "EPD_C11") (pin "1") (pinfunction "1_1") (pintype "passive"))
      (node (ref "J1") (pin "23") (pinfunction "23_23") (pintype "bidirectional"))
    )
    (net (code "41") (name "RESE") (class "Default")
      (node (ref "J1") (pin "3") (pinfunction "3_3") (pintype "bidirectional"))
      (node (ref "Q3") (pin "2") (pinfunction "S_2") (pintype "bidirectional"))
      (node (ref "R3") (pin "1") (pinfunction "1_1") (pintype "passive"))
    )
    (net (code "42") (name "RESE'") (class "Default")
      (node (ref "R2") (pin "2") (pinfunction "2_2") (pintype "passive"))
      (node (ref "R3") (pin "2") (pinfunction "2_2") (pintype "passive"))
      (node (ref "SJ1") (pin "2") (pinfunction "2_2") (pintype "passive"))
    )
    (net (code "43") (name "RESET") (class "Default")
      (node (ref "C5") (pin "1") (pinfunction "1_1") (pintype "passive"))
      (node (ref "IC1") (pin "1") (pinfunction "VOUT_1") (pintype "bidirectional"))
      (node (ref "RESET_BUTTON") (pin "3") (pinfunction "3_3") (pintype "passive"))
      (node (ref "RESET_BUTTON") (pin "4") (pinfunction "4_4") (pintype "passive"))
      (node (ref "R_RESET") (pin "2") (pinfunction "2_2") (pintype "passive"))
      (node (ref "U2") (pin "3") (pinfunction "EN_3") (pintype "input"))
    )
    (net (code "44") (name "RTC_RST") (class "Default")
      (node (ref "U2") (pin "16") (pinfunction "IO18_16") (pintype "bidirectional"))
      (node (ref "U3") (pin "4") (pinfunction "~{RST}_4") (pintype "input"))
    )
    (net (code "45") (name "RX") (class "Default")
      (node (ref "RX") (pin "TP") (pinfunction "TP_TP") (pintype "input"))
      (node (ref "U2") (pin "24") (pinfunction "RXD0/GPIO17_24") (pintype "bidirectional"))
    )
    (net (code "46") (name "SCA") (class "Default")
      (node (ref "J3") (pin "3") (pinfunction "3_3") (pintype "passive"))
    )
    (net (code "47") (name "SCD") (class "Default")
      (node (ref "J3") (pin "4") (pinfunction "4_4") (pintype "passive"))
    )
    (net (code "48") (name "SCK") (class "Default")
      (node (ref "D10") (pin "2") (pinfunction "2_2") (pintype "passive"))
      (node (ref "J1") (pin "13") (pinfunction "13_13") (pintype "bidirectional"))
      (node (ref "J4") (pin "P5") (pinfunction "CLK_P5") (pintype "bidirectional"))
      (node (ref "R6") (pin "1") (pinfunction "1_1") (pintype "passive"))
      (node (ref "SCK") (pin "TP") (pinfunction "TP_TP") (pintype "input"))
      (node (ref "U1") (pin "6") (pinfunction "CLK_6") (pintype "input"))
      (node (ref "U2") (pin "6") (pinfunction "IO6_6") (pintype "bidirectional"))
    )
    (net (code "49") (name "SCL") (class "Default")
      (node (ref "R2-PINH") (pin "1") (pinfunction "1_1") (pintype "passive"))
      (node (ref "SENSOR2") (pin "4") (pinfunction "SCK_4") (pintype "input"))
      (node (ref "U2") (pin "20") (pinfunction "IO22_20") (pintype "bidirectional"))
      (node (ref "U3") (pin "16") (pinfunction "SCL_16") (pintype "input"))
      (node (ref "U4") (pin "7") (pinfunction "SCL_7") (pintype "input"))
    )
    (net (code "50") (name "SDA") (class "Default")
      (node (ref "R1-PINH") (pin "1") (pinfunction "1_1") (pintype "passive"))
      (node (ref "SENSOR2") (pin "3") (pinfunction "SDI_3") (pintype "bidirectional"))
      (node (ref "U2") (pin "19") (pinfunction "IO21_19") (pintype "bidirectional"))
      (node (ref "U3") (pin "15") (pinfunction "SDA_15") (pintype "bidirectional"))
      (node (ref "U4") (pin "8") (pinfunction "SDA_8") (pintype "bidirectional"))
    )
    (net (code "51") (name "SRC") (class "Default")
      (node (ref "Q3") (pin "3") (pinfunction "D_3") (pintype "bidirectional"))
    )
    (net (code "52") (name "SS_SD") (class "Default")
      (node (ref "D8") (pin "2") (pinfunction "2_2") (pintype "passive"))
      (node (ref "J4") (pin "P2") (pinfunction "CD/DAT3_P2") (pintype "bidirectional"))
      (node (ref "R10") (pin "1") (pinfunction "1_1") (pintype "passive"))
      (node (ref "U2") (pin "4") (pinfunction "IO4_4") (pintype "bidirectional"))
    )
    (net (code "53") (name "TX") (class "Default")
      (node (ref "TX") (pin "TP") (pinfunction "TP_TP") (pintype "input"))
      (node (ref "U2") (pin "25") (pinfunction "TXD0/GPIO16_25") (pintype "bidirectional"))
    )
    (net (code "54") (name "USB_D+") (class "Default")
      (node (ref "D1") (pin "4") (pinfunction "I/O2_2_4") (pintype "bidirectional"))
      (node (ref "U2") (pin "14") (pinfunction "IO13_14") (pintype "bidirectional"))
    )
    (net (code "55") (name "USB_D-") (class "Default")
      (node (ref "D1") (pin "6") (pinfunction "I/O1_2_6") (pintype "bidirectional"))
      (node (ref "U2") (pin "13") (pinfunction "IO12_13") (pintype "bidirectional"))
    )
    (net (code "56") (name "VBAT") (class "Default")
      (node (ref "C2_BAT") (pin "1") (pinfunction "1_1") (pintype "passive"))
      (node (ref "Q1") (pin "3") (pinfunction "D_3") (pintype "bidirectional"))
      (node (ref "U4") (pin "2") (pinfunction "CELL_2") (pintype "power_in"))
      (node (ref "U4") (pin "3") (pinfunction "VDD_3") (pintype "power_in"))
      (node (ref "U5") (pin "3") (pinfunction "VBAT_3") (pintype "power_in"))
      (node (ref "VBAT") (pin "TP") (pinfunction "TP_TP") (pintype "input"))
    )
    (net (code "57") (name "VBUS") (class "Default")
      (node (ref "C1_BAT") (pin "1") (pinfunction "1_1") (pintype "passive"))
      (node (ref "C4_USB") (pin "1") (pinfunction "1_1") (pintype "passive"))
      (node (ref "C5_USB") (pin "1") (pinfunction "1_1") (pintype "passive"))
      (node (ref "CHG_LED") (pin "A") (pinfunction "A_A") (pintype "passive"))
      (node (ref "D1") (pin "2") (pinfunction "GND_2") (pintype "bidirectional"))
      (node (ref "D2") (pin "2") (pinfunction "ANODE_2") (pintype "bidirectional"))
      (node (ref "PFMF.050.1") (pin "2") (pinfunction "2_2") (pintype "passive"))
      (node (ref "Q1") (pin "1") (pinfunction "G_1") (pintype "bidirectional"))
      (node (ref "R1_PWRUSB") (pin "1") (pinfunction "1_1") (pintype "passive"))
      (node (ref "U5") (pin "4") (pinfunction "VIN_4") (pintype "power_in"))
      (node (ref "VBUS") (pin "TP") (pinfunction "TP_TP") (pintype "input"))
    )
    (net (code "58") (name "VRTC") (class "Default")
      (node (ref "C10_SUPERCAP") (pin "2") (pinfunction "2_2") (pintype "passive"))
      (node (ref "C8") (pin "1") (pinfunction "1_1") (pintype "passive"))
      (node (ref "R_CAPACITOR") (pin "1") (pinfunction "1_1") (pintype "passive"))
      (node (ref "U3") (pin "14") (pinfunction "VBAT_14") (pintype "power_in"))
    )
    (net (code "59") (name "VUSB") (class "Default")
      (node (ref "J2") (pin "A4") (pinfunction "A4_A4") (pintype "bidirectional"))
      (node (ref "J2") (pin "A9") (pinfunction "A9_A9") (pintype "bidirectional"))
      (node (ref "J2") (pin "B4") (pinfunction "B4_B4") (pintype "bidirectional"))
      (node (ref "J2") (pin "B9") (pinfunction "B9_B9") (pintype "bidirectional"))
      (node (ref "PFMF.050.1") (pin "1") (pinfunction "1_1") (pintype "passive"))
    )
    (net (code "60") (name "unconnected-(IC1-NC-Pad4)") (class "Default")
      (node (ref "IC1") (pin "4") (pinfunction "NC_4") (pintype "no_connect"))
    )
    (net (code "61") (name "unconnected-(IC4-NC-Pad4)") (class "Default")
      (node (ref "IC4") (pin "4") (pinfunction "NC_4") (pintype "no_connect"))
    )
    (net (code "62") (name "unconnected-(J1-Pad1)") (class "Default")
      (node (ref "J1") (pin "1") (pinfunction "1_1") (pintype "bidirectional"))
    )
    (net (code "63") (name "unconnected-(J1-Pad6)") (class "Default")
      (node (ref "J1") (pin "6") (pinfunction "6_6") (pintype "bidirectional"))
    )
    (net (code "64") (name "unconnected-(J1-Pad7)") (class "Default")
      (node (ref "J1") (pin "7") (pinfunction "7_7") (pintype "bidirectional"))
    )
    (net (code "65") (name "unconnected-(J1-Pad8)") (class "Default")
      (node (ref "J1") (pin "8") (pinfunction "8_8") (pintype "bidirectional"))
    )
    (net (code "66") (name "unconnected-(J2-PadA8)") (class "Default")
      (node (ref "J2") (pin "A8") (pinfunction "A8_A8") (pintype "bidirectional"))
    )
    (net (code "67") (name "unconnected-(J2-PadB8)") (class "Default")
      (node (ref "J2") (pin "B8") (pinfunction "B8_B8") (pintype "bidirectional"))
    )
    (net (code "68") (name "unconnected-(J4-DAT1-PadP8)") (class "Default")
      (node (ref "J4") (pin "P8") (pinfunction "DAT1_P8") (pintype "bidirectional"))
    )
    (net (code "69") (name "unconnected-(J4-DAT2-PadP1)") (class "Default")
      (node (ref "J4") (pin "P1") (pinfunction "DAT2_P1") (pintype "bidirectional"))
    )
    (net (code "70") (name "unconnected-(J4-DETECTION_1-PadS1)") (class "Default")
      (node (ref "J4") (pin "S1") (pinfunction "DETECTION_1_S1") (pintype "bidirectional"))
    )
    (net (code "71") (name "unconnected-(J4-DETECTION_2-PadS2)") (class "Default")
      (node (ref "J4") (pin "S2") (pinfunction "DETECTION_2_S2") (pintype "bidirectional"))
    )
    (net (code "72") (name "unconnected-(U2-NC-Pad22)") (class "Default")
      (node (ref "U2") (pin "22") (pinfunction "NC_22") (pintype "no_connect"))
    )
    (net (code "73") (name "unconnected-(U4-~{ALERT}-Pad5)") (class "Default")
      (node (ref "U4") (pin "5") (pinfunction "~{ALERT}_5") (pintype "output"))
    )
  )
)
